# MCU.net
KiCad netlist of a schematic drawn in Altium Designer
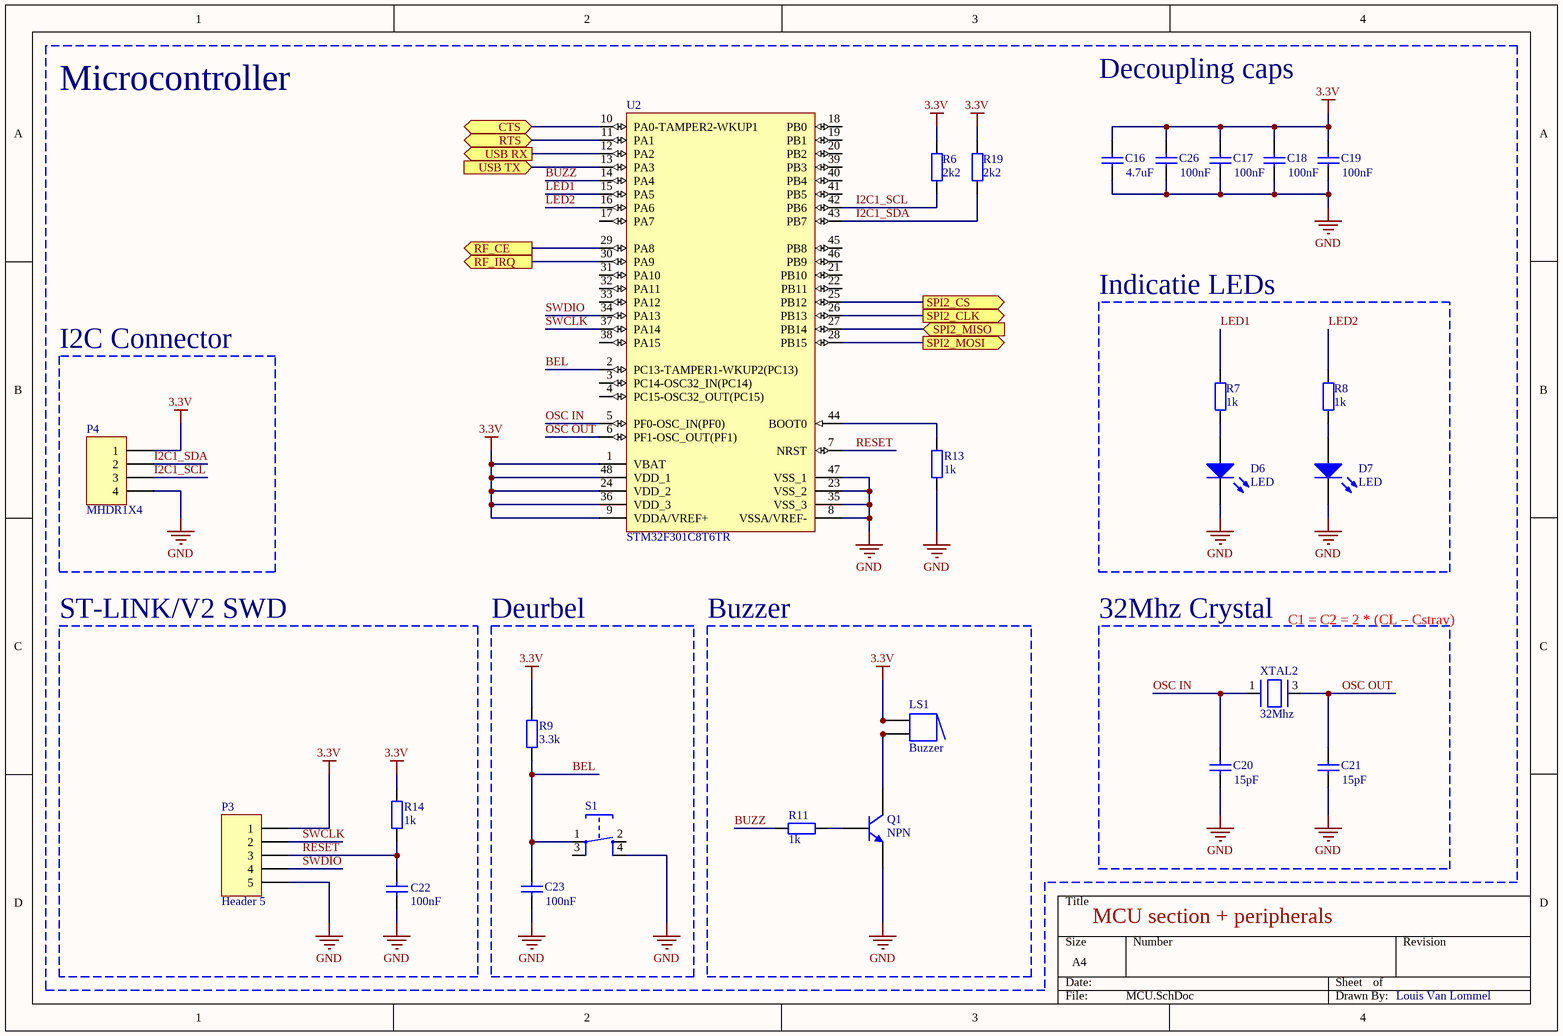
[diagram p0: MCU.SchDoc]

(export (version "E")
  (design (tool "Eeschema 10.0.6"))
  (components
    (comp (ref "C16")
      (value "4.7uF")
      (footprint "CAP_0603")
      (description "Capacitor")
      (fields (field (name "PUBLISHER") "Altium Limited"))
      (libsource (lib "Miscellaneous Devices") (part "Cap"))
    )
    (comp (ref "C17")
      (value "100nF")
      (footprint "CAP_0603")
      (description "Capacitor")
      (fields (field (name "PUBLISHER") "Altium Limited"))
      (libsource (lib "Miscellaneous Devices") (part "Cap"))
    )
    (comp (ref "C18")
      (value "100nF")
      (footprint "CAP_0603")
      (description "Capacitor")
      (fields (field (name "PUBLISHER") "Altium Limited"))
      (libsource (lib "Miscellaneous Devices") (part "Cap"))
    )
    (comp (ref "C19")
      (value "100nF")
      (footprint "CAP_0603")
      (description "Capacitor")
      (fields (field (name "PUBLISHER") "Altium Limited"))
      (libsource (lib "Miscellaneous Devices") (part "Cap"))
    )
    (comp (ref "C20")
      (value "15pF")
      (footprint "CAP_0603")
      (description "Capacitor")
      (fields (field (name "PUBLISHER") "Altium Limited"))
      (libsource (lib "Miscellaneous Devices") (part "Cap"))
    )
    (comp (ref "C21")
      (value "15pF")
      (footprint "CAP_0603")
      (description "Capacitor")
      (fields (field (name "PUBLISHER") "Altium Limited"))
      (libsource (lib "Miscellaneous Devices") (part "Cap"))
    )
    (comp (ref "C22")
      (value "100nF")
      (footprint "CAP_0603")
      (description "Capacitor")
      (fields (field (name "PUBLISHER") "Altium Limited"))
      (libsource (lib "Miscellaneous Devices") (part "Cap"))
    )
    (comp (ref "C23")
      (value "100nF")
      (footprint "CAP_0603")
      (description "Capacitor")
      (fields (field (name "PUBLISHER") "Altium Limited"))
      (libsource (lib "Miscellaneous Devices") (part "Cap"))
    )
    (comp (ref "C26")
      (value "100nF")
      (footprint "CAP_0603")
      (description "Capacitor")
      (fields (field (name "PUBLISHER") "Altium Limited"))
      (libsource (lib "Miscellaneous Devices") (part "Cap"))
    )
    (comp (ref "D6")
      (value "LED")
      (footprint "LED_0603")
      (description "Typical RED, GREEN, YELLOW, AMBER GaAs LED")
      (fields (field (name "PUBLISHER") "Altium Limited"))
      (libsource (lib "Miscellaneous Devices") (part "LED2"))
    )
    (comp (ref "D7")
      (value "LED")
      (footprint "LED_0603")
      (description "Typical RED, GREEN, YELLOW, AMBER GaAs LED")
      (fields (field (name "PUBLISHER") "Altium Limited"))
      (libsource (lib "Miscellaneous Devices") (part "LED2"))
    )
    (comp (ref "LS1")
      (value "Buzzer")
      (footprint "Buzzer")
      (description "Magnetic Transducer Buzzer")
      (fields (field (name "PUBLISHER") "Altium Limited"))
      (libsource (lib "Buzzer") (part "Buzzer"))
    )
    (comp (ref "P3")
      (value "Header 5")
      (footprint "HDR1X5")
      (description "Header, 5-Pin")
      (fields (field (name "PUBLISHER") "Altium Limited"))
      (libsource (lib "Miscellaneous Connectors") (part "Header 5"))
    )
    (comp (ref "P4")
      (value "MHDR1X4")
      (footprint "MHDR1X4")
      (description "Header, 4-Pin")
      (fields (field (name "PUBLISHER") "Altium Limited"))
      (libsource (lib "Miscellaneous Connectors") (part "MHDR1X4"))
    )
    (comp (ref "Q1")
      (value "NPN")
      (footprint "SOT23_L")
      (description "NPN Bipolar Transistor")
      (fields (field (name "PUBLISHER") "Altium Limited"))
      (libsource (lib "Miscellaneous Devices") (part "NPN"))
    )
    (comp (ref "R6")
      (value "2k2")
      (footprint "RES_0603")
      (description "Resistor")
      (fields (field (name "PUBLISHER") "Altium Limited"))
      (libsource (lib "Miscellaneous Devices") (part "Res2"))
    )
    (comp (ref "R7")
      (value "1k")
      (footprint "RES_0603")
      (description "Resistor")
      (fields (field (name "PUBLISHER") "Altium Limited"))
      (libsource (lib "Miscellaneous Devices") (part "Res2"))
    )
    (comp (ref "R8")
      (value "1k")
      (footprint "RES_0603")
      (description "Resistor")
      (fields (field (name "PUBLISHER") "Altium Limited"))
      (libsource (lib "Miscellaneous Devices") (part "Res2"))
    )
    (comp (ref "R9")
      (value "3.3k")
      (footprint "RES_0603")
      (description "Resistor")
      (fields (field (name "PUBLISHER") "Altium Limited"))
      (libsource (lib "") (part "Res2_2"))
    )
    (comp (ref "R11")
      (value "1k")
      (footprint "RES_0603")
      (description "Resistor")
      (fields (field (name "PUBLISHER") "Altium Limited"))
      (libsource (lib "") (part "Res2_1"))
    )
    (comp (ref "R13")
      (value "1k")
      (footprint "RES_0603")
      (description "Resistor")
      (fields (field (name "PUBLISHER") "Altium Limited"))
      (libsource (lib "") (part "Res2_2"))
    )
    (comp (ref "R14")
      (value "1k")
      (footprint "RES_0603")
      (description "Resistor")
      (fields (field (name "PUBLISHER") "Altium Limited"))
      (libsource (lib "") (part "Res2_2"))
    )
    (comp (ref "R19")
      (value "2k2")
      (footprint "RES_0603")
      (description "Resistor")
      (fields (field (name "PUBLISHER") "Altium Limited"))
      (libsource (lib "Miscellaneous Devices") (part "Res2"))
    )
    (comp (ref "S1")
      (value "~")
      (footprint "TactileSwitch6x6")
      (description "gekruisde schakelaar (1.4 en 2.3)")
      (libsource (lib "PE2_Schematics") (part "Tactile Switch"))
    )
    (comp (ref "U2")
      (value "STM32F301C8T6TR")
      (footprint "STM-LQFP48_M")
      (libsource (lib "Altium Content Vault") (part "MC-ARM-STM32F30X-LQFP48"))
    )
    (comp (ref "XTAL2")
      (value "32Mhz")
      (footprint "16Mhz_Crystal")
      (description "Crystal, 16 MHz, SMD, 3.2mm x 2.5mm, 30 ppm, 18 pF, 30 ppm, 7M")
      (libsource (lib "AP2112") (part "Crystal"))
    )
  )
  (nets
    (net (code "1") (name "/BEL") (class "Default")
      (node (ref "C23") (pin "2") (pinfunction "2_2") (pintype "passive"))
      (node (ref "R9") (pin "2") (pinfunction "2_2") (pintype "passive"))
      (node (ref "S1") (pin "1") (pintype "passive"))
      (node (ref "U2") (pin "2") (pinfunction "PC13-TAMPER1-WKUP2(PC13)_2") (pintype "bidirectional"))
    )
    (net (code "2") (name "/BUZZ") (class "Default")
      (node (ref "R11") (pin "1") (pinfunction "1_1") (pintype "passive"))
      (node (ref "U2") (pin "14") (pinfunction "PA4_14") (pintype "bidirectional"))
    )
    (net (code "3") (name "/CTS") (class "Default")
      (node (ref "U2") (pin "10") (pinfunction "PA0-TAMPER2-WKUP1_10") (pintype "bidirectional"))
    )
    (net (code "4") (name "/I2C1_SCL") (class "Default")
      (node (ref "P4") (pin "3") (pinfunction "3_3") (pintype "passive"))
      (node (ref "R6") (pin "1") (pinfunction "1_1") (pintype "passive"))
      (node (ref "U2") (pin "42") (pinfunction "PB6_42") (pintype "bidirectional"))
    )
    (net (code "5") (name "/I2C1_SDA") (class "Default")
      (node (ref "P4") (pin "2") (pinfunction "2_2") (pintype "passive"))
      (node (ref "R19") (pin "1") (pinfunction "1_1") (pintype "passive"))
      (node (ref "U2") (pin "43") (pinfunction "PB7_43") (pintype "bidirectional"))
    )
    (net (code "6") (name "/LED1") (class "Default")
      (node (ref "R7") (pin "2") (pinfunction "2_2") (pintype "passive"))
      (node (ref "U2") (pin "15") (pinfunction "PA5_15") (pintype "bidirectional"))
    )
    (net (code "7") (name "/LED2") (class "Default")
      (node (ref "R8") (pin "2") (pinfunction "2_2") (pintype "passive"))
      (node (ref "U2") (pin "16") (pinfunction "PA6_16") (pintype "bidirectional"))
    )
    (net (code "8") (name "/OSC IN") (class "Default")
      (node (ref "C20") (pin "2") (pinfunction "2_2") (pintype "passive"))
      (node (ref "U2") (pin "5") (pinfunction "PF0-OSC_IN(PF0)_5") (pintype "bidirectional"))
      (node (ref "XTAL2") (pin "1") (pinfunction "1_1") (pintype "passive"))
    )
    (net (code "9") (name "/OSC OUT") (class "Default")
      (node (ref "C21") (pin "2") (pinfunction "2_2") (pintype "passive"))
      (node (ref "U2") (pin "6") (pinfunction "PF1-OSC_OUT(PF1)_6") (pintype "bidirectional"))
      (node (ref "XTAL2") (pin "3") (pinfunction "3_3") (pintype "passive"))
    )
    (net (code "10") (name "/RESET") (class "Default")
      (node (ref "C22") (pin "2") (pinfunction "2_2") (pintype "passive"))
      (node (ref "P3") (pin "3") (pinfunction "3_3") (pintype "passive"))
      (node (ref "R14") (pin "2") (pinfunction "2_2") (pintype "passive"))
      (node (ref "U2") (pin "7") (pinfunction "NRST_7") (pintype "bidirectional"))
    )
    (net (code "11") (name "/RF_CE") (class "Default")
      (node (ref "U2") (pin "29") (pinfunction "PA8_29") (pintype "bidirectional"))
    )
    (net (code "12") (name "/RF_IRQ") (class "Default")
      (node (ref "U2") (pin "30") (pinfunction "PA9_30") (pintype "bidirectional"))
    )
    (net (code "13") (name "/RTS") (class "Default")
      (node (ref "U2") (pin "11") (pinfunction "PA1_11") (pintype "bidirectional"))
    )
    (net (code "14") (name "/SPI2_CLK") (class "Default")
      (node (ref "U2") (pin "26") (pinfunction "PB13_26") (pintype "bidirectional"))
    )
    (net (code "15") (name "/SPI2_CS") (class "Default")
      (node (ref "U2") (pin "25") (pinfunction "PB12_25") (pintype "bidirectional"))
    )
    (net (code "16") (name "/SPI2_MISO") (class "Default")
      (node (ref "U2") (pin "27") (pinfunction "PB14_27") (pintype "bidirectional"))
    )
    (net (code "17") (name "/SPI2_MOSI") (class "Default")
      (node (ref "U2") (pin "28") (pinfunction "PB15_28") (pintype "bidirectional"))
    )
    (net (code "18") (name "/SWCLK") (class "Default")
      (node (ref "P3") (pin "2") (pinfunction "2_2") (pintype "passive"))
      (node (ref "U2") (pin "37") (pinfunction "PA14_37") (pintype "bidirectional"))
    )
    (net (code "19") (name "/SWDIO") (class "Default")
      (node (ref "P3") (pin "4") (pinfunction "4_4") (pintype "passive"))
      (node (ref "U2") (pin "34") (pinfunction "PA13_34") (pintype "bidirectional"))
    )
    (net (code "20") (name "/USB RX") (class "Default")
      (node (ref "U2") (pin "12") (pinfunction "PA2_12") (pintype "bidirectional"))
    )
    (net (code "21") (name "/USB TX") (class "Default")
      (node (ref "U2") (pin "13") (pinfunction "PA3_13") (pintype "bidirectional"))
    )
    (net (code "22") (name "3.3V") (class "Default")
      (node (ref "C16") (pin "2") (pinfunction "2_2") (pintype "passive"))
      (node (ref "C17") (pin "2") (pinfunction "2_2") (pintype "passive"))
      (node (ref "C18") (pin "2") (pinfunction "2_2") (pintype "passive"))
      (node (ref "C19") (pin "2") (pinfunction "2_2") (pintype "passive"))
      (node (ref "C26") (pin "2") (pinfunction "2_2") (pintype "passive"))
      (node (ref "LS1") (pin "1") (pinfunction "1_1") (pintype "passive"))
      (node (ref "LS1") (pin "1A") (pinfunction "1A_1A") (pintype "passive"))
      (node (ref "P3") (pin "1") (pinfunction "1_1") (pintype "passive"))
      (node (ref "P4") (pin "1") (pinfunction "1_1") (pintype "passive"))
      (node (ref "R14") (pin "1") (pinfunction "1_1") (pintype "passive"))
      (node (ref "R19") (pin "2") (pinfunction "2_2") (pintype "passive"))
      (node (ref "R6") (pin "2") (pinfunction "2_2") (pintype "passive"))
      (node (ref "R9") (pin "1") (pinfunction "1_1") (pintype "passive"))
      (node (ref "U2") (pin "1") (pinfunction "VBAT_1") (pintype "power_in"))
      (node (ref "U2") (pin "24") (pinfunction "VDD_2_24") (pintype "power_in"))
      (node (ref "U2") (pin "36") (pinfunction "VDD_3_36") (pintype "power_in"))
      (node (ref "U2") (pin "48") (pinfunction "VDD_1_48") (pintype "power_in"))
      (node (ref "U2") (pin "9") (pinfunction "VDDA/VREF+_9") (pintype "power_in"))
    )
    (net (code "23") (name "GND") (class "Default")
      (node (ref "C16") (pin "1") (pinfunction "1_1") (pintype "passive"))
      (node (ref "C17") (pin "1") (pinfunction "1_1") (pintype "passive"))
      (node (ref "C18") (pin "1") (pinfunction "1_1") (pintype "passive"))
      (node (ref "C19") (pin "1") (pinfunction "1_1") (pintype "passive"))
      (node (ref "C20") (pin "1") (pinfunction "1_1") (pintype "passive"))
      (node (ref "C21") (pin "1") (pinfunction "1_1") (pintype "passive"))
      (node (ref "C22") (pin "1") (pinfunction "1_1") (pintype "passive"))
      (node (ref "C23") (pin "1") (pinfunction "1_1") (pintype "passive"))
      (node (ref "C26") (pin "1") (pinfunction "1_1") (pintype "passive"))
      (node (ref "D6") (pin "2") (pinfunction "K_2") (pintype "passive"))
      (node (ref "D7") (pin "2") (pinfunction "K_2") (pintype "passive"))
      (node (ref "P3") (pin "5") (pinfunction "5_5") (pintype "passive"))
      (node (ref "P4") (pin "4") (pinfunction "4_4") (pintype "passive"))
      (node (ref "Q1") (pin "3") (pinfunction "E_3") (pintype "passive"))
      (node (ref "R13") (pin "2") (pinfunction "2_2") (pintype "passive"))
      (node (ref "S1") (pin "4") (pintype "passive"))
      (node (ref "U2") (pin "23") (pinfunction "VSS_2_23") (pintype "power_in"))
      (node (ref "U2") (pin "35") (pinfunction "VSS_3_35") (pintype "power_in"))
      (node (ref "U2") (pin "47") (pinfunction "VSS_1_47") (pintype "power_in"))
      (node (ref "U2") (pin "8") (pinfunction "VSSA/VREF-_8") (pintype "power_in"))
    )
    (net (code "24") (name "Net-(D6-A)") (class "Default")
      (node (ref "D6") (pin "1") (pinfunction "A_1") (pintype "passive"))
      (node (ref "R7") (pin "1") (pinfunction "1_1") (pintype "passive"))
    )
    (net (code "25") (name "Net-(D7-A)") (class "Default")
      (node (ref "D7") (pin "1") (pinfunction "A_1") (pintype "passive"))
      (node (ref "R8") (pin "1") (pinfunction "1_1") (pintype "passive"))
    )
    (net (code "26") (name "Net-(Q1-B)") (class "Default")
      (node (ref "Q1") (pin "2") (pinfunction "B_2") (pintype "passive"))
      (node (ref "R11") (pin "2") (pinfunction "2_2") (pintype "passive"))
    )
    (net (code "27") (name "Net-(Q1-C)") (class "Default")
      (node (ref "LS1") (pin "2") (pinfunction "2_2") (pintype "passive"))
      (node (ref "LS1") (pin "2A") (pinfunction "2A_2A") (pintype "passive"))
      (node (ref "Q1") (pin "1") (pinfunction "C_1") (pintype "passive"))
    )
    (net (code "28") (name "Net-(U2-BOOT0)") (class "Default")
      (node (ref "R13") (pin "1") (pinfunction "1_1") (pintype "passive"))
      (node (ref "U2") (pin "44") (pinfunction "BOOT0_44") (pintype "input"))
    )
    (net (code "29") (name "unconnected-(S1-Pad2)") (class "Default")
      (node (ref "S1") (pin "2") (pintype "passive"))
    )
    (net (code "30") (name "unconnected-(S1-Pad3)") (class "Default")
      (node (ref "S1") (pin "3") (pintype "passive"))
    )
    (net (code "31") (name "unconnected-(U2-PA7-Pad17)") (class "Default")
      (node (ref "U2") (pin "17") (pinfunction "PA7_17") (pintype "bidirectional"))
    )
    (net (code "32") (name "unconnected-(U2-PA10-Pad31)") (class "Default")
      (node (ref "U2") (pin "31") (pinfunction "PA10_31") (pintype "bidirectional"))
    )
    (net (code "33") (name "unconnected-(U2-PA11-Pad32)") (class "Default")
      (node (ref "U2") (pin "32") (pinfunction "PA11_32") (pintype "bidirectional"))
    )
    (net (code "34") (name "unconnected-(U2-PA12-Pad33)") (class "Default")
      (node (ref "U2") (pin "33") (pinfunction "PA12_33") (pintype "bidirectional"))
    )
    (net (code "35") (name "unconnected-(U2-PA15-Pad38)") (class "Default")
      (node (ref "U2") (pin "38") (pinfunction "PA15_38") (pintype "bidirectional"))
    )
    (net (code "36") (name "unconnected-(U2-PB0-Pad18)") (class "Default")
      (node (ref "U2") (pin "18") (pinfunction "PB0_18") (pintype "bidirectional"))
    )
    (net (code "37") (name "unconnected-(U2-PB1-Pad19)") (class "Default")
      (node (ref "U2") (pin "19") (pinfunction "PB1_19") (pintype "bidirectional"))
    )
    (net (code "38") (name "unconnected-(U2-PB2-Pad20)") (class "Default")
      (node (ref "U2") (pin "20") (pinfunction "PB2_20") (pintype "bidirectional"))
    )
    (net (code "39") (name "unconnected-(U2-PB3-Pad39)") (class "Default")
      (node (ref "U2") (pin "39") (pinfunction "PB3_39") (pintype "bidirectional"))
    )
    (net (code "40") (name "unconnected-(U2-PB4-Pad40)") (class "Default")
      (node (ref "U2") (pin "40") (pinfunction "PB4_40") (pintype "bidirectional"))
    )
    (net (code "41") (name "unconnected-(U2-PB5-Pad41)") (class "Default")
      (node (ref "U2") (pin "41") (pinfunction "PB5_41") (pintype "bidirectional"))
    )
    (net (code "42") (name "unconnected-(U2-PB8-Pad45)") (class "Default")
      (node (ref "U2") (pin "45") (pinfunction "PB8_45") (pintype "bidirectional"))
    )
    (net (code "43") (name "unconnected-(U2-PB9-Pad46)") (class "Default")
      (node (ref "U2") (pin "46") (pinfunction "PB9_46") (pintype "bidirectional"))
    )
    (net (code "44") (name "unconnected-(U2-PB10-Pad21)") (class "Default")
      (node (ref "U2") (pin "21") (pinfunction "PB10_21") (pintype "bidirectional"))
    )
    (net (code "45") (name "unconnected-(U2-PB11-Pad22)") (class "Default")
      (node (ref "U2") (pin "22") (pinfunction "PB11_22") (pintype "bidirectional"))
    )
    (net (code "46") (name "unconnected-(U2-PC14-OSC32_IN(PC14)-Pad3)") (class "Default")
      (node (ref "U2") (pin "3") (pinfunction "PC14-OSC32_IN(PC14)_3") (pintype "bidirectional"))
    )
    (net (code "47") (name "unconnected-(U2-PC15-OSC32_OUT(PC15)-Pad4)") (class "Default")
      (node (ref "U2") (pin "4") (pinfunction "PC15-OSC32_OUT(PC15)_4") (pintype "bidirectional"))
    )
  )
)
